# smd.net
KiCad netlist of a schematic drawn in EAGLE
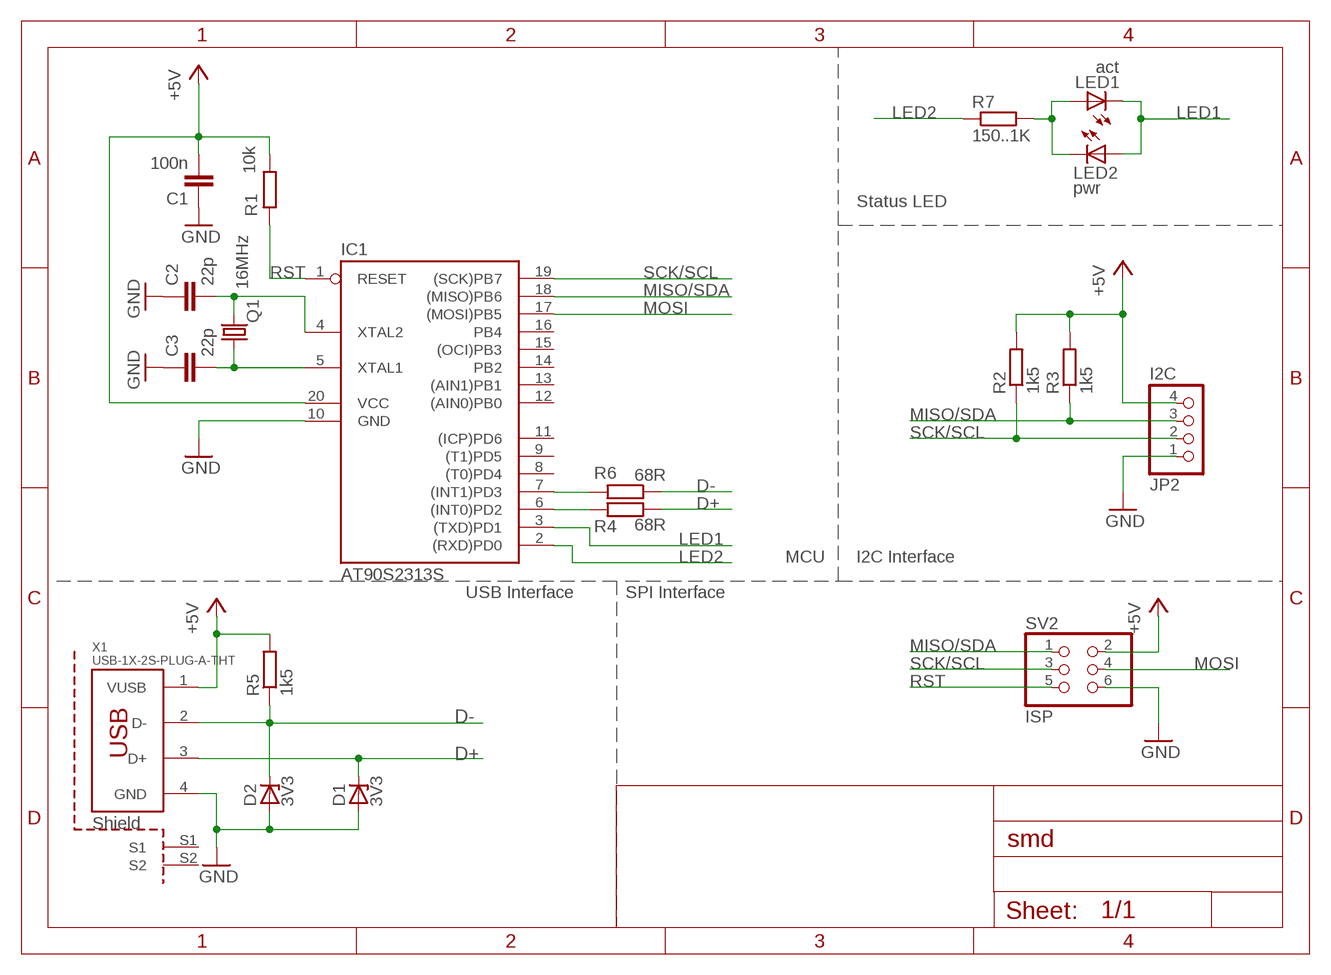
[diagram p0: schematic, sheet 1]

(export (version "E")
  (design (tool "Eeschema 10.0.6"))
  (components
    (comp (ref "C1")
      (value "100n")
      (footprint "eagle-import:C0805")
      (libsource (lib "eagle-import") (part "C-EUC0805"))
    )
    (comp (ref "C2")
      (value "22p")
      (footprint "eagle-import:C0805")
      (libsource (lib "eagle-import") (part "C-EUC0805"))
    )
    (comp (ref "C3")
      (value "22p")
      (footprint "eagle-import:C0805")
      (libsource (lib "eagle-import") (part "C-EUC0805"))
    )
    (comp (ref "D1")
      (value "3V3")
      (footprint "eagle-import:SOD80C")
      (libsource (lib "eagle-import") (part "ZENER-DIODESOD80C"))
    )
    (comp (ref "D2")
      (value "3V3")
      (footprint "eagle-import:SOD80C")
      (libsource (lib "eagle-import") (part "ZENER-DIODESOD80C"))
    )
    (comp (ref "IC1")
      (value "AT90S2313S")
      (footprint "eagle-import:SO20L")
      (libsource (lib "eagle-import") (part "AT90S2313S"))
    )
    (comp (ref "JP2")
      (value "I2C")
      (footprint "eagle-import:1X04")
      (libsource (lib "eagle-import") (part "PINHD-1X4"))
    )
    (comp (ref "LED1")
      (value "act")
      (footprint "eagle-import:SML0805")
      (libsource (lib "eagle-import") (part "LEDSML0805"))
    )
    (comp (ref "LED2")
      (value "pwr")
      (footprint "eagle-import:SML0805")
      (libsource (lib "eagle-import") (part "LEDSML0805"))
    )
    (comp (ref "Q1")
      (value "16MHz")
      (footprint "eagle-import:HC49_S")
      (libsource (lib "eagle-import") (part "CRYTALHC49S"))
    )
    (comp (ref "R1")
      (value "10k")
      (footprint "eagle-import:R0805")
      (libsource (lib "eagle-import") (part "R-EU_R0805"))
    )
    (comp (ref "R2")
      (value "1k5")
      (footprint "eagle-import:R0805")
      (libsource (lib "eagle-import") (part "R-EU_R0805"))
    )
    (comp (ref "R3")
      (value "1k5")
      (footprint "eagle-import:R0805")
      (libsource (lib "eagle-import") (part "R-EU_R0805"))
    )
    (comp (ref "R4")
      (value "68R")
      (footprint "eagle-import:R0805")
      (libsource (lib "eagle-import") (part "R-EU_R0805"))
    )
    (comp (ref "R5")
      (value "1k5")
      (footprint "eagle-import:R0805")
      (libsource (lib "eagle-import") (part "R-EU_R0805"))
    )
    (comp (ref "R6")
      (value "68R")
      (footprint "eagle-import:R0805")
      (libsource (lib "eagle-import") (part "R-EU_R0805"))
    )
    (comp (ref "R7")
      (value "150..1K")
      (footprint "eagle-import:R0805")
      (libsource (lib "eagle-import") (part "R-EU_R0805"))
    )
    (comp (ref "SV2")
      (value "ISP")
      (footprint "eagle-import:2X03")
      (libsource (lib "eagle-import") (part "PINHD-2X3"))
    )
    (comp (ref "X1")
      (value "USB-1X-2S-PLUG-A-THT")
      (footprint "eagle-import:USB-PLUG-A-THT-2S")
      (libsource (lib "eagle-import") (part "USB-1X-2S-PLUG-A-THT"))
    )
  )
  (nets
    (net (code "1") (name "+5V") (class "Default")
      (node (ref "C1") (pin "2") (pinfunction "2_2") (pintype "passive"))
      (node (ref "IC1") (pin "20") (pinfunction "VCC_20") (pintype "power_in"))
      (node (ref "JP2") (pin "4") (pinfunction "4_4") (pintype "passive"))
      (node (ref "R1") (pin "2") (pinfunction "2_2") (pintype "passive"))
      (node (ref "R2") (pin "2") (pinfunction "2_2") (pintype "passive"))
      (node (ref "R3") (pin "2") (pinfunction "2_2") (pintype "passive"))
      (node (ref "R5") (pin "2") (pinfunction "2_2") (pintype "passive"))
      (node (ref "SV2") (pin "2") (pinfunction "2_2") (pintype "passive"))
      (node (ref "X1") (pin "1") (pinfunction "VUSB_1") (pintype "passive"))
    )
    (net (code "2") (name "/D+") (class "Default")
      (node (ref "D1") (pin "C") (pinfunction "C_C") (pintype "passive"))
      (node (ref "R4") (pin "1") (pinfunction "1_1") (pintype "passive"))
      (node (ref "X1") (pin "3") (pinfunction "D+_3") (pintype "passive"))
    )
    (net (code "3") (name "/D-") (class "Default")
      (node (ref "D2") (pin "C") (pinfunction "C_C") (pintype "passive"))
      (node (ref "R5") (pin "1") (pinfunction "1_1") (pintype "passive"))
      (node (ref "R6") (pin "1") (pinfunction "1_1") (pintype "passive"))
      (node (ref "X1") (pin "2") (pinfunction "D-_2") (pintype "passive"))
    )
    (net (code "4") (name "/LED1") (class "Default")
      (node (ref "IC1") (pin "3") (pinfunction "(TXD)PD1_3") (pintype "bidirectional"))
      (node (ref "LED1") (pin "C") (pinfunction "C_C") (pintype "passive"))
      (node (ref "LED2") (pin "A") (pinfunction "A_A") (pintype "passive"))
    )
    (net (code "5") (name "/LED2") (class "Default")
      (node (ref "IC1") (pin "2") (pinfunction "(RXD)PD0_2") (pintype "bidirectional"))
      (node (ref "R7") (pin "1") (pinfunction "1_1") (pintype "passive"))
    )
    (net (code "6") (name "/MISO{slash}SDA") (class "Default")
      (node (ref "IC1") (pin "18") (pinfunction "(MISO)PB6_18") (pintype "bidirectional"))
      (node (ref "JP2") (pin "3") (pinfunction "3_3") (pintype "passive"))
      (node (ref "R3") (pin "1") (pinfunction "1_1") (pintype "passive"))
      (node (ref "SV2") (pin "1") (pinfunction "1_1") (pintype "passive"))
    )
    (net (code "7") (name "/MOSI") (class "Default")
      (node (ref "IC1") (pin "17") (pinfunction "(MOSI)PB5_17") (pintype "bidirectional"))
      (node (ref "SV2") (pin "4") (pinfunction "4_4") (pintype "passive"))
    )
    (net (code "8") (name "/RST") (class "Default")
      (node (ref "IC1") (pin "1") (pinfunction "RESET_1") (pintype "bidirectional"))
      (node (ref "R1") (pin "1") (pinfunction "1_1") (pintype "passive"))
      (node (ref "SV2") (pin "5") (pinfunction "5_5") (pintype "passive"))
    )
    (net (code "9") (name "/SCK{slash}SCL") (class "Default")
      (node (ref "IC1") (pin "19") (pinfunction "(SCK)PB7_19") (pintype "bidirectional"))
      (node (ref "JP2") (pin "2") (pinfunction "2_2") (pintype "passive"))
      (node (ref "R2") (pin "1") (pinfunction "1_1") (pintype "passive"))
      (node (ref "SV2") (pin "3") (pinfunction "3_3") (pintype "passive"))
    )
    (net (code "10") (name "GND") (class "Default")
      (node (ref "C1") (pin "1") (pinfunction "1_1") (pintype "passive"))
      (node (ref "C2") (pin "1") (pinfunction "1_1") (pintype "passive"))
      (node (ref "C3") (pin "1") (pinfunction "1_1") (pintype "passive"))
      (node (ref "D1") (pin "A") (pinfunction "A_A") (pintype "passive"))
      (node (ref "D2") (pin "A") (pinfunction "A_A") (pintype "passive"))
      (node (ref "IC1") (pin "10") (pinfunction "GND_10") (pintype "power_in"))
      (node (ref "JP2") (pin "1") (pinfunction "1_1") (pintype "passive"))
      (node (ref "SV2") (pin "6") (pinfunction "6_6") (pintype "passive"))
      (node (ref "X1") (pin "4") (pinfunction "GND_4") (pintype "passive"))
    )
    (net (code "11") (name "Net-(IC1-(INT0)PD2)") (class "Default")
      (node (ref "IC1") (pin "6") (pinfunction "(INT0)PD2_6") (pintype "bidirectional"))
      (node (ref "R4") (pin "2") (pinfunction "2_2") (pintype "passive"))
    )
    (net (code "12") (name "Net-(IC1-(INT1)PD3)") (class "Default")
      (node (ref "IC1") (pin "7") (pinfunction "(INT1)PD3_7") (pintype "bidirectional"))
      (node (ref "R6") (pin "2") (pinfunction "2_2") (pintype "passive"))
    )
    (net (code "13") (name "Net-(IC1-XTAL1)") (class "Default")
      (node (ref "C3") (pin "2") (pinfunction "2_2") (pintype "passive"))
      (node (ref "IC1") (pin "5") (pinfunction "XTAL1_5") (pintype "bidirectional"))
      (node (ref "Q1") (pin "1") (pinfunction "1_1") (pintype "passive"))
    )
    (net (code "14") (name "Net-(IC1-XTAL2)") (class "Default")
      (node (ref "C2") (pin "2") (pinfunction "2_2") (pintype "passive"))
      (node (ref "IC1") (pin "4") (pinfunction "XTAL2_4") (pintype "bidirectional"))
      (node (ref "Q1") (pin "2") (pinfunction "2_2") (pintype "passive"))
    )
    (net (code "15") (name "Net-(LED1-PadA)") (class "Default")
      (node (ref "LED1") (pin "A") (pinfunction "A_A") (pintype "passive"))
      (node (ref "LED2") (pin "C") (pinfunction "C_C") (pintype "passive"))
      (node (ref "R7") (pin "2") (pinfunction "2_2") (pintype "passive"))
    )
    (net (code "16") (name "unconnected-(IC1-(AIN0)PB0-Pad12)") (class "Default")
      (node (ref "IC1") (pin "12") (pinfunction "(AIN0)PB0_12") (pintype "bidirectional"))
    )
    (net (code "17") (name "unconnected-(IC1-(AIN1)PB1-Pad13)") (class "Default")
      (node (ref "IC1") (pin "13") (pinfunction "(AIN1)PB1_13") (pintype "bidirectional"))
    )
    (net (code "18") (name "unconnected-(IC1-(ICP)PD6-Pad11)") (class "Default")
      (node (ref "IC1") (pin "11") (pinfunction "(ICP)PD6_11") (pintype "bidirectional"))
    )
    (net (code "19") (name "unconnected-(IC1-(OCI)PB3-Pad15)") (class "Default")
      (node (ref "IC1") (pin "15") (pinfunction "(OCI)PB3_15") (pintype "bidirectional"))
    )
    (net (code "20") (name "unconnected-(IC1-(T0)PD4-Pad8)") (class "Default")
      (node (ref "IC1") (pin "8") (pinfunction "(T0)PD4_8") (pintype "bidirectional"))
    )
    (net (code "21") (name "unconnected-(IC1-(T1)PD5-Pad9)") (class "Default")
      (node (ref "IC1") (pin "9") (pinfunction "(T1)PD5_9") (pintype "bidirectional"))
    )
    (net (code "22") (name "unconnected-(IC1-PB2-Pad14)") (class "Default")
      (node (ref "IC1") (pin "14") (pinfunction "PB2_14") (pintype "bidirectional"))
    )
    (net (code "23") (name "unconnected-(IC1-PB4-Pad16)") (class "Default")
      (node (ref "IC1") (pin "16") (pinfunction "PB4_16") (pintype "bidirectional"))
    )
    (net (code "24") (name "unconnected-(X1-PadS1)") (class "Default")
      (node (ref "X1") (pin "S1") (pinfunction "S1_S1") (pintype "passive"))
    )
    (net (code "25") (name "unconnected-(X1-PadS2)") (class "Default")
      (node (ref "X1") (pin "S2") (pinfunction "S2_S2") (pintype "passive"))
    )
  )
)
